# relay_din_board.net
KiCad netlist of a schematic drawn in EAGLE
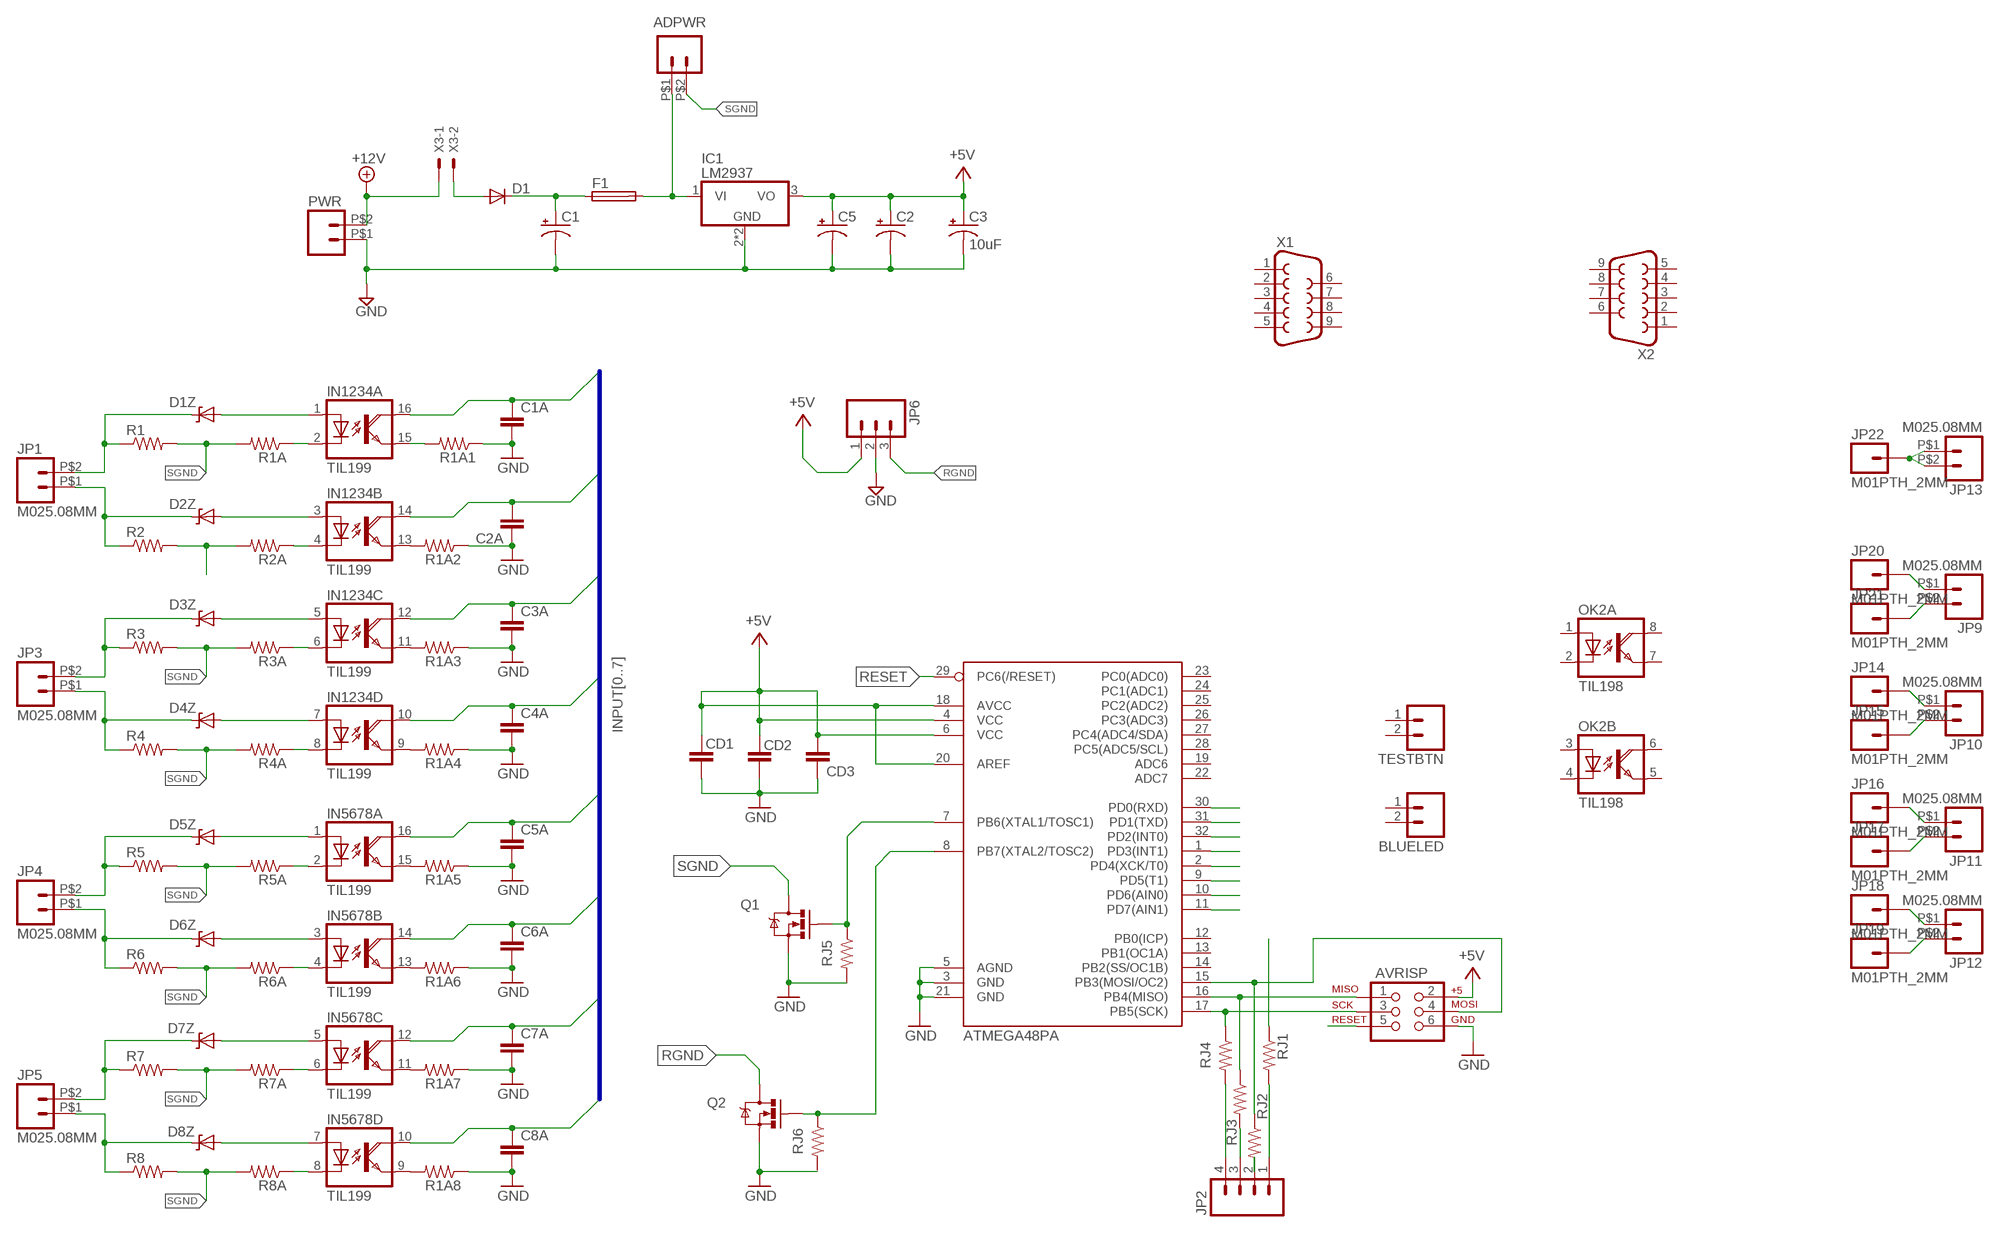
[diagram p0: schematic, sheet 1]

(export (version "E")
  (design (tool "Eeschema 10.0.6"))
  (components
    (comp (ref "ADPWR")
      (value "M025.08MM")
      (footprint "eagle-import:SCREWTERMINAL-5.08MM-2")
      (libsource (lib "eagle-import") (part "M025.08MM"))
    )
    (comp (ref "ATMEGA48PA")
      (value "ATMEGA168")
      (footprint "eagle-import:TQFP32-08")
      (libsource (lib "eagle-import") (part "ATMEGA168"))
    )
    (comp (ref "AVRISP")
      (value "AVR_SPI_PRG_6PTH")
      (footprint "eagle-import:2X3")
      (libsource (lib "eagle-import") (part "AVR_SPI_PRG_6PTH"))
    )
    (comp (ref "BLUELED")
      (value "M02PTH")
      (footprint "eagle-import:1X02")
      (libsource (lib "eagle-import") (part "M02PTH"))
    )
    (comp (ref "C1")
      (value "CPOL-USE5-10.5")
      (footprint "eagle-import:E5-10,5")
      (libsource (lib "eagle-import") (part "CPOL-USE5-10.5"))
    )
    (comp (ref "C1A")
      (value "CAP0805")
      (footprint "eagle-import:0805")
      (libsource (lib "eagle-import") (part "CAP0805"))
    )
    (comp (ref "C2")
      (value "CPOL-US153CLV-0605")
      (footprint "eagle-import:153CLV-0605")
      (libsource (lib "eagle-import") (part "CPOL-US153CLV-0605"))
    )
    (comp (ref "C2A")
      (value "CAP0805")
      (footprint "eagle-import:0805")
      (libsource (lib "eagle-import") (part "CAP0805"))
    )
    (comp (ref "C3")
      (value "10uF")
      (footprint "eagle-import:EIA3216")
      (libsource (lib "eagle-import") (part "10UF-TANT"))
    )
    (comp (ref "C3A")
      (value "CAP0805")
      (footprint "eagle-import:0805")
      (libsource (lib "eagle-import") (part "CAP0805"))
    )
    (comp (ref "C4A")
      (value "CAP0805")
      (footprint "eagle-import:0805")
      (libsource (lib "eagle-import") (part "CAP0805"))
    )
    (comp (ref "C5")
      (value "CPOL-US153CLV-0605")
      (footprint "eagle-import:153CLV-0605")
      (libsource (lib "eagle-import") (part "CPOL-US153CLV-0605"))
    )
    (comp (ref "C5A")
      (value "CAP0805")
      (footprint "eagle-import:0805")
      (libsource (lib "eagle-import") (part "CAP0805"))
    )
    (comp (ref "C6A")
      (value "CAP0805")
      (footprint "eagle-import:0805")
      (libsource (lib "eagle-import") (part "CAP0805"))
    )
    (comp (ref "C7A")
      (value "CAP0805")
      (footprint "eagle-import:0805")
      (libsource (lib "eagle-import") (part "CAP0805"))
    )
    (comp (ref "C8A")
      (value "CAP0805")
      (footprint "eagle-import:0805")
      (libsource (lib "eagle-import") (part "CAP0805"))
    )
    (comp (ref "CD1")
      (value "CAP0805")
      (footprint "eagle-import:0805")
      (libsource (lib "eagle-import") (part "CAP0805"))
    )
    (comp (ref "CD2")
      (value "CAP0805")
      (footprint "eagle-import:0805")
      (libsource (lib "eagle-import") (part "CAP0805"))
    )
    (comp (ref "CD3")
      (value "CAP0805")
      (footprint "eagle-import:0805")
      (libsource (lib "eagle-import") (part "CAP0805"))
    )
    (comp (ref "D1")
      (value "DIODE-C1702-05")
      (footprint "eagle-import:C1702-05")
      (libsource (lib "eagle-import") (part "DIODE-C1702-05"))
    )
    (comp (ref "D1Z")
      (value "DIODE-ZENER-BZT52")
      (footprint "eagle-import:SOD-323")
      (libsource (lib "eagle-import") (part "DIODE-ZENER-BZT52"))
    )
    (comp (ref "D2Z")
      (value "DIODE-ZENER-BZT52")
      (footprint "eagle-import:SOD-323")
      (libsource (lib "eagle-import") (part "DIODE-ZENER-BZT52"))
    )
    (comp (ref "D3Z")
      (value "DIODE-ZENER-BZT52")
      (footprint "eagle-import:SOD-323")
      (libsource (lib "eagle-import") (part "DIODE-ZENER-BZT52"))
    )
    (comp (ref "D4Z")
      (value "DIODE-ZENER-BZT52")
      (footprint "eagle-import:SOD-323")
      (libsource (lib "eagle-import") (part "DIODE-ZENER-BZT52"))
    )
    (comp (ref "D5Z")
      (value "DIODE-ZENER-BZT52")
      (footprint "eagle-import:SOD-323")
      (libsource (lib "eagle-import") (part "DIODE-ZENER-BZT52"))
    )
    (comp (ref "D6Z")
      (value "DIODE-ZENER-BZT52")
      (footprint "eagle-import:SOD-323")
      (libsource (lib "eagle-import") (part "DIODE-ZENER-BZT52"))
    )
    (comp (ref "D7Z")
      (value "DIODE-ZENER-BZT52")
      (footprint "eagle-import:SOD-323")
      (libsource (lib "eagle-import") (part "DIODE-ZENER-BZT52"))
    )
    (comp (ref "D8Z")
      (value "DIODE-ZENER-BZT52")
      (footprint "eagle-import:SOD-323")
      (libsource (lib "eagle-import") (part "DIODE-ZENER-BZT52"))
    )
    (comp (ref "F1")
      (value "GSH15")
      (footprint "eagle-import:GSH15")
      (fields (field (name "MPN") "64900001039"))
      (libsource (lib "eagle-import") (part "GSH15"))
    )
    (comp (ref "IC1")
      (value "LM2937")
      (footprint "eagle-import:TO263-3")
      (libsource (lib "eagle-import") (part "LM2937"))
    )
    (comp (ref "IN1234")
      (value "TIL199")
      (footprint "eagle-import:DIL16")
      (fields (field (name "MPN") "TIL 199"))
      (libsource (lib "eagle-import") (part "TIL199"))
    )
    (comp (ref "IN5678")
      (value "TIL199")
      (footprint "eagle-import:DIL16")
      (fields (field (name "MPN") "TIL 199"))
      (libsource (lib "eagle-import") (part "TIL199"))
    )
    (comp (ref "JP1")
      (value "M025.08MM")
      (footprint "eagle-import:SCREWTERMINAL-5.08MM-2")
      (libsource (lib "eagle-import") (part "M025.08MM"))
    )
    (comp (ref "JP2")
      (value "M04PTH")
      (footprint "eagle-import:1X04")
      (libsource (lib "eagle-import") (part "M04PTH"))
    )
    (comp (ref "JP3")
      (value "M025.08MM")
      (footprint "eagle-import:SCREWTERMINAL-5.08MM-2")
      (libsource (lib "eagle-import") (part "M025.08MM"))
    )
    (comp (ref "JP4")
      (value "M025.08MM")
      (footprint "eagle-import:SCREWTERMINAL-5.08MM-2")
      (libsource (lib "eagle-import") (part "M025.08MM"))
    )
    (comp (ref "JP5")
      (value "M025.08MM")
      (footprint "eagle-import:SCREWTERMINAL-5.08MM-2")
      (libsource (lib "eagle-import") (part "M025.08MM"))
    )
    (comp (ref "JP6")
      (value "M03PTH")
      (footprint "eagle-import:1X03")
      (libsource (lib "eagle-import") (part "M03PTH"))
    )
    (comp (ref "JP9")
      (value "M025.08MM")
      (footprint "eagle-import:SCREWTERMINAL-5.08MM-2")
      (libsource (lib "eagle-import") (part "M025.08MM"))
    )
    (comp (ref "JP10")
      (value "M025.08MM")
      (footprint "eagle-import:SCREWTERMINAL-5.08MM-2")
      (libsource (lib "eagle-import") (part "M025.08MM"))
    )
    (comp (ref "JP11")
      (value "M025.08MM")
      (footprint "eagle-import:SCREWTERMINAL-5.08MM-2")
      (libsource (lib "eagle-import") (part "M025.08MM"))
    )
    (comp (ref "JP12")
      (value "M025.08MM")
      (footprint "eagle-import:SCREWTERMINAL-5.08MM-2")
      (libsource (lib "eagle-import") (part "M025.08MM"))
    )
    (comp (ref "JP13")
      (value "M025.08MM")
      (footprint "eagle-import:SCREWTERMINAL-5.08MM-2")
      (libsource (lib "eagle-import") (part "M025.08MM"))
    )
    (comp (ref "JP14")
      (value "M01PTH_2MM")
      (footprint "eagle-import:1X01_2MM")
      (libsource (lib "eagle-import") (part "M01PTH_2MM"))
    )
    (comp (ref "JP15")
      (value "M01PTH_2MM")
      (footprint "eagle-import:1X01_2MM")
      (libsource (lib "eagle-import") (part "M01PTH_2MM"))
    )
    (comp (ref "JP16")
      (value "M01PTH_2MM")
      (footprint "eagle-import:1X01_2MM")
      (libsource (lib "eagle-import") (part "M01PTH_2MM"))
    )
    (comp (ref "JP17")
      (value "M01PTH_2MM")
      (footprint "eagle-import:1X01_2MM")
      (libsource (lib "eagle-import") (part "M01PTH_2MM"))
    )
    (comp (ref "JP18")
      (value "M01PTH_2MM")
      (footprint "eagle-import:1X01_2MM")
      (libsource (lib "eagle-import") (part "M01PTH_2MM"))
    )
    (comp (ref "JP19")
      (value "M01PTH_2MM")
      (footprint "eagle-import:1X01_2MM")
      (libsource (lib "eagle-import") (part "M01PTH_2MM"))
    )
    (comp (ref "JP20")
      (value "M01PTH_2MM")
      (footprint "eagle-import:1X01_2MM")
      (libsource (lib "eagle-import") (part "M01PTH_2MM"))
    )
    (comp (ref "JP21")
      (value "M01PTH_2MM")
      (footprint "eagle-import:1X01_2MM")
      (libsource (lib "eagle-import") (part "M01PTH_2MM"))
    )
    (comp (ref "JP22")
      (value "M01PTH_2MM")
      (footprint "eagle-import:1X01_2MM")
      (libsource (lib "eagle-import") (part "M01PTH_2MM"))
    )
    (comp (ref "OK2")
      (value "TIL198")
      (footprint "eagle-import:DIL08")
      (libsource (lib "eagle-import") (part "TIL198"))
    )
    (comp (ref "PWR")
      (value "M025.08MM")
      (footprint "eagle-import:SCREWTERMINAL-5.08MM-2")
      (libsource (lib "eagle-import") (part "M025.08MM"))
    )
    (comp (ref "Q1")
      (value "MOSFET-NCHANNELBSS123LT1G")
      (footprint "eagle-import:SOT23")
      (libsource (lib "eagle-import") (part "MOSFET-NCHANNELBSS123LT1G"))
    )
    (comp (ref "Q2")
      (value "MOSFET-NCHANNELBSS123LT1G")
      (footprint "eagle-import:SOT23")
      (libsource (lib "eagle-import") (part "MOSFET-NCHANNELBSS123LT1G"))
    )
    (comp (ref "R1")
      (value "RESISTOR2512")
      (footprint "eagle-import:R2512")
      (libsource (lib "eagle-import") (part "RESISTOR2512"))
    )
    (comp (ref "R1A")
      (value "RESISTOR0805-RES")
      (footprint "eagle-import:0805")
      (libsource (lib "eagle-import") (part "SparkFun-Resistors_RESISTOR0805-RES"))
    )
    (comp (ref "R1A1")
      (value "RESISTOR0805-RES")
      (footprint "eagle-import:0805")
      (libsource (lib "eagle-import") (part "SparkFun-Resistors_RESISTOR0805-RES"))
    )
    (comp (ref "R1A2")
      (value "RESISTOR0805-RES")
      (footprint "eagle-import:0805")
      (libsource (lib "eagle-import") (part "SparkFun-Resistors_RESISTOR0805-RES"))
    )
    (comp (ref "R1A3")
      (value "RESISTOR0805-RES")
      (footprint "eagle-import:0805")
      (libsource (lib "eagle-import") (part "SparkFun-Resistors_RESISTOR0805-RES"))
    )
    (comp (ref "R1A4")
      (value "RESISTOR0805-RES")
      (footprint "eagle-import:0805")
      (libsource (lib "eagle-import") (part "SparkFun-Resistors_RESISTOR0805-RES"))
    )
    (comp (ref "R1A5")
      (value "RESISTOR0805-RES")
      (footprint "eagle-import:0805")
      (libsource (lib "eagle-import") (part "SparkFun-Resistors_RESISTOR0805-RES"))
    )
    (comp (ref "R1A6")
      (value "RESISTOR0805-RES")
      (footprint "eagle-import:0805")
      (libsource (lib "eagle-import") (part "SparkFun-Resistors_RESISTOR0805-RES"))
    )
    (comp (ref "R1A7")
      (value "RESISTOR0805-RES")
      (footprint "eagle-import:0805")
      (libsource (lib "eagle-import") (part "SparkFun-Resistors_RESISTOR0805-RES"))
    )
    (comp (ref "R1A8")
      (value "RESISTOR0805-RES")
      (footprint "eagle-import:0805")
      (libsource (lib "eagle-import") (part "SparkFun-Resistors_RESISTOR0805-RES"))
    )
    (comp (ref "R2")
      (value "RESISTOR2512")
      (footprint "eagle-import:R2512")
      (libsource (lib "eagle-import") (part "RESISTOR2512"))
    )
    (comp (ref "R2A")
      (value "RESISTOR0805-RES")
      (footprint "eagle-import:0805")
      (libsource (lib "eagle-import") (part "SparkFun-Resistors_RESISTOR0805-RES"))
    )
    (comp (ref "R3")
      (value "RESISTOR2512")
      (footprint "eagle-import:R2512")
      (libsource (lib "eagle-import") (part "RESISTOR2512"))
    )
    (comp (ref "R3A")
      (value "RESISTOR0805-RES")
      (footprint "eagle-import:0805")
      (libsource (lib "eagle-import") (part "SparkFun-Resistors_RESISTOR0805-RES"))
    )
    (comp (ref "R4")
      (value "RESISTOR2512")
      (footprint "eagle-import:R2512")
      (libsource (lib "eagle-import") (part "RESISTOR2512"))
    )
    (comp (ref "R4A")
      (value "RESISTOR0805-RES")
      (footprint "eagle-import:0805")
      (libsource (lib "eagle-import") (part "SparkFun-Resistors_RESISTOR0805-RES"))
    )
    (comp (ref "R5")
      (value "RESISTOR2512")
      (footprint "eagle-import:R2512")
      (libsource (lib "eagle-import") (part "RESISTOR2512"))
    )
    (comp (ref "R5A")
      (value "RESISTOR0805-RES")
      (footprint "eagle-import:0805")
      (libsource (lib "eagle-import") (part "SparkFun-Resistors_RESISTOR0805-RES"))
    )
    (comp (ref "R6")
      (value "RESISTOR2512")
      (footprint "eagle-import:R2512")
      (libsource (lib "eagle-import") (part "RESISTOR2512"))
    )
    (comp (ref "R6A")
      (value "RESISTOR0805-RES")
      (footprint "eagle-import:0805")
      (libsource (lib "eagle-import") (part "SparkFun-Resistors_RESISTOR0805-RES"))
    )
    (comp (ref "R7")
      (value "RESISTOR2512")
      (footprint "eagle-import:R2512")
      (libsource (lib "eagle-import") (part "RESISTOR2512"))
    )
    (comp (ref "R7A")
      (value "RESISTOR0805-RES")
      (footprint "eagle-import:0805")
      (libsource (lib "eagle-import") (part "SparkFun-Resistors_RESISTOR0805-RES"))
    )
    (comp (ref "R8")
      (value "RESISTOR2512")
      (footprint "eagle-import:R2512")
      (libsource (lib "eagle-import") (part "RESISTOR2512"))
    )
    (comp (ref "R8A")
      (value "RESISTOR0805-RES")
      (footprint "eagle-import:0805")
      (libsource (lib "eagle-import") (part "SparkFun-Resistors_RESISTOR0805-RES"))
    )
    (comp (ref "RJ1")
      (value "RESISTOR0805-RES")
      (footprint "eagle-import:0805")
      (libsource (lib "eagle-import") (part "SparkFun-Resistors_RESISTOR0805-RES"))
    )
    (comp (ref "RJ2")
      (value "RESISTOR0805-RES")
      (footprint "eagle-import:0805")
      (libsource (lib "eagle-import") (part "SparkFun-Resistors_RESISTOR0805-RES"))
    )
    (comp (ref "RJ3")
      (value "RESISTOR0805-RES")
      (footprint "eagle-import:0805")
      (libsource (lib "eagle-import") (part "SparkFun-Resistors_RESISTOR0805-RES"))
    )
    (comp (ref "RJ4")
      (value "RESISTOR0805-RES")
      (footprint "eagle-import:0805")
      (libsource (lib "eagle-import") (part "SparkFun-Resistors_RESISTOR0805-RES"))
    )
    (comp (ref "RJ5")
      (value "RESISTOR0805-RES")
      (footprint "eagle-import:0805")
      (libsource (lib "eagle-import") (part "SparkFun-Resistors_RESISTOR0805-RES"))
    )
    (comp (ref "RJ6")
      (value "RESISTOR0805-RES")
      (footprint "eagle-import:0805")
      (libsource (lib "eagle-import") (part "SparkFun-Resistors_RESISTOR0805-RES"))
    )
    (comp (ref "TESTBTN")
      (value "M02PTH")
      (footprint "eagle-import:1X02")
      (libsource (lib "eagle-import") (part "M02PTH"))
    )
    (comp (ref "X1")
      (value "DB9FEMALE")
      (footprint "eagle-import:DB9")
      (libsource (lib "eagle-import") (part "DB9FEMALE"))
    )
    (comp (ref "X2")
      (value "DB9MALE")
      (footprint "eagle-import:DB9_MALE")
      (libsource (lib "eagle-import") (part "DB9MALE"))
    )
    (comp (ref "X3")
      (value "22-23-2021")
      (footprint "eagle-import:22-23-2021")
      (fields (field (name "MF") "MOLEX"))
      (libsource (lib "eagle-import") (part "22-23-2021"))
    )
  )
  (nets
    (net (code "1") (name "+5V") (class "Default")
      (node (ref "ATMEGA48PA") (pin "18") (pinfunction "AVCC_18") (pintype "bidirectional"))
      (node (ref "ATMEGA48PA") (pin "20") (pinfunction "AREF_20") (pintype "bidirectional"))
      (node (ref "ATMEGA48PA") (pin "4") (pinfunction "VCC_4") (pintype "bidirectional"))
      (node (ref "ATMEGA48PA") (pin "6") (pinfunction "VCC_6") (pintype "bidirectional"))
      (node (ref "AVRISP") (pin "2") (pinfunction "2_2") (pintype "passive"))
      (node (ref "C2") (pin "+") (pinfunction "+_+") (pintype "passive"))
      (node (ref "C3") (pin "A") (pinfunction "+_A") (pintype "passive"))
      (node (ref "C5") (pin "+") (pinfunction "+_+") (pintype "passive"))
      (node (ref "CD1") (pin "1") (pinfunction "1_1") (pintype "passive"))
      (node (ref "CD2") (pin "1") (pinfunction "1_1") (pintype "passive"))
      (node (ref "CD3") (pin "1") (pinfunction "1_1") (pintype "passive"))
      (node (ref "IC1") (pin "3") (pinfunction "VO_3") (pintype "passive"))
      (node (ref "JP6") (pin "1") (pinfunction "1_1") (pintype "passive"))
    )
    (net (code "2") (name "+12V") (class "Default")
      (node (ref "PWR") (pin "P$2") (pinfunction "2_P$2") (pintype "passive"))
      (node (ref "X3") (pin "1") (pinfunction "S_1") (pintype "passive"))
    )
    (net (code "3") (name "/INPUT0") (class "Default")
      (node (ref "ATMEGA48PA") (pin "30") (pinfunction "PD0(RXD)_30") (pintype "bidirectional"))
      (node (ref "C1A") (pin "1") (pinfunction "1_1") (pintype "passive"))
      (node (ref "IN1234") (pin "16") (pinfunction "COL_16") (pintype "passive"))
    )
    (net (code "4") (name "/INPUT1") (class "Default")
      (node (ref "ATMEGA48PA") (pin "31") (pinfunction "PD1(TXD)_31") (pintype "bidirectional"))
      (node (ref "C2A") (pin "2") (pinfunction "2_2") (pintype "passive"))
      (node (ref "IN1234") (pin "14") (pinfunction "COL_14") (pintype "passive"))
    )
    (net (code "5") (name "/INPUT2") (class "Default")
      (node (ref "ATMEGA48PA") (pin "32") (pinfunction "PD2(INT0)_32") (pintype "bidirectional"))
      (node (ref "C3A") (pin "1") (pinfunction "1_1") (pintype "passive"))
      (node (ref "IN1234") (pin "12") (pinfunction "COL_12") (pintype "passive"))
    )
    (net (code "6") (name "/INPUT3") (class "Default")
      (node (ref "ATMEGA48PA") (pin "1") (pinfunction "PD3(INT1)_1") (pintype "bidirectional"))
      (node (ref "C4A") (pin "1") (pinfunction "1_1") (pintype "passive"))
      (node (ref "IN1234") (pin "10") (pinfunction "COL_10") (pintype "passive"))
    )
    (net (code "7") (name "/INPUT4") (class "Default")
      (node (ref "ATMEGA48PA") (pin "2") (pinfunction "PD4(XCK/T0)_2") (pintype "bidirectional"))
      (node (ref "C5A") (pin "1") (pinfunction "1_1") (pintype "passive"))
      (node (ref "IN5678") (pin "16") (pinfunction "COL_16") (pintype "passive"))
    )
    (net (code "8") (name "/INPUT5") (class "Default")
      (node (ref "ATMEGA48PA") (pin "9") (pinfunction "PD5(T1)_9") (pintype "bidirectional"))
      (node (ref "C6A") (pin "1") (pinfunction "1_1") (pintype "passive"))
      (node (ref "IN5678") (pin "14") (pinfunction "COL_14") (pintype "passive"))
    )
    (net (code "9") (name "/INPUT6") (class "Default")
      (node (ref "ATMEGA48PA") (pin "10") (pinfunction "PD6(AIN0)_10") (pintype "bidirectional"))
      (node (ref "C7A") (pin "1") (pinfunction "1_1") (pintype "passive"))
      (node (ref "IN5678") (pin "12") (pinfunction "COL_12") (pintype "passive"))
    )
    (net (code "10") (name "/INPUT7") (class "Default")
      (node (ref "ATMEGA48PA") (pin "11") (pinfunction "PD7(AIN1)_11") (pintype "bidirectional"))
      (node (ref "C8A") (pin "1") (pinfunction "1_1") (pintype "passive"))
      (node (ref "IN5678") (pin "10") (pinfunction "COL_10") (pintype "passive"))
    )
    (net (code "12") (name "GND") (class "Default")
      (node (ref "ATMEGA48PA") (pin "21") (pinfunction "GND_21") (pintype "bidirectional"))
      (node (ref "ATMEGA48PA") (pin "3") (pinfunction "GND_3") (pintype "bidirectional"))
      (node (ref "ATMEGA48PA") (pin "5") (pinfunction "AGND_5") (pintype "bidirectional"))
      (node (ref "AVRISP") (pin "6") (pinfunction "6_6") (pintype "passive"))
      (node (ref "C1") (pin "-") (pinfunction "-_-") (pintype "passive"))
      (node (ref "C1A") (pin "2") (pinfunction "2_2") (pintype "passive"))
      (node (ref "C2") (pin "-") (pinfunction "-_-") (pintype "passive"))
      (node (ref "C2A") (pin "1") (pinfunction "1_1") (pintype "passive"))
      (node (ref "C3") (pin "C") (pinfunction "-_C") (pintype "passive"))
      (node (ref "C3A") (pin "2") (pinfunction "2_2") (pintype "passive"))
      (node (ref "C4A") (pin "2") (pinfunction "2_2") (pintype "passive"))
      (node (ref "C5") (pin "-") (pinfunction "-_-") (pintype "passive"))
      (node (ref "C5A") (pin "2") (pinfunction "2_2") (pintype "passive"))
      (node (ref "C6A") (pin "2") (pinfunction "2_2") (pintype "passive"))
      (node (ref "C7A") (pin "2") (pinfunction "2_2") (pintype "passive"))
      (node (ref "C8A") (pin "2") (pinfunction "2_2") (pintype "passive"))
      (node (ref "CD1") (pin "2") (pinfunction "2_2") (pintype "passive"))
      (node (ref "CD2") (pin "2") (pinfunction "2_2") (pintype "passive"))
      (node (ref "CD3") (pin "2") (pinfunction "2_2") (pintype "passive"))
      (node (ref "IC1") (pin "2") (pinfunction "GND_2") (pintype "passive"))
      (node (ref "IC1") (pin "TAB") (pinfunction "GND_TAB") (pintype "passive"))
      (node (ref "JP6") (pin "2") (pinfunction "2_2") (pintype "passive"))
      (node (ref "PWR") (pin "P$1") (pinfunction "1_P$1") (pintype "passive"))
      (node (ref "Q1") (pin "2") (pinfunction "S_2") (pintype "passive"))
      (node (ref "Q2") (pin "2") (pinfunction "S_2") (pintype "passive"))
      (node (ref "R1A1") (pin "1") (pinfunction "1_1") (pintype "passive"))
      (node (ref "R1A2") (pin "1") (pinfunction "1_1") (pintype "passive"))
      (node (ref "R1A3") (pin "1") (pinfunction "1_1") (pintype "passive"))
      (node (ref "R1A4") (pin "1") (pinfunction "1_1") (pintype "passive"))
      (node (ref "R1A5") (pin "1") (pinfunction "1_1") (pintype "passive"))
      (node (ref "R1A6") (pin "1") (pinfunction "1_1") (pintype "passive"))
      (node (ref "R1A7") (pin "1") (pinfunction "1_1") (pintype "passive"))
      (node (ref "R1A8") (pin "1") (pinfunction "1_1") (pintype "passive"))
      (node (ref "RJ5") (pin "2") (pinfunction "2_2") (pintype "passive"))
    )
    (net (code "13") (name "Net-(ADPWR-1)") (class "Default")
      (node (ref "ADPWR") (pin "P$1") (pinfunction "1_P$1") (pintype "passive"))
      (node (ref "F1") (pin "2") (pinfunction "2_2") (pintype "passive"))
      (node (ref "IC1") (pin "1") (pinfunction "VI_1") (pintype "input"))
    )
    (net (code "14") (name "Net-(ATMEGA48PA-PB3(MOSI{slash}OC2))") (class "Default")
      (node (ref "ATMEGA48PA") (pin "15") (pinfunction "PB3(MOSI/OC2)_15") (pintype "bidirectional"))
      (node (ref "AVRISP") (pin "4") (pinfunction "4_4") (pintype "passive"))
      (node (ref "RJ2") (pin "1") (pinfunction "1_1") (pintype "passive"))
    )
    (net (code "15") (name "Net-(ATMEGA48PA-PB4(MISO))") (class "Default")
      (node (ref "ATMEGA48PA") (pin "16") (pinfunction "PB4(MISO)_16") (pintype "bidirectional"))
      (node (ref "AVRISP") (pin "1") (pinfunction "1_1") (pintype "passive"))
      (node (ref "RJ3") (pin "1") (pinfunction "1_1") (pintype "passive"))
    )
    (net (code "16") (name "Net-(ATMEGA48PA-PB5(SCK))") (class "Default")
      (node (ref "ATMEGA48PA") (pin "17") (pinfunction "PB5(SCK)_17") (pintype "bidirectional"))
      (node (ref "AVRISP") (pin "3") (pinfunction "3_3") (pintype "passive"))
      (node (ref "RJ4") (pin "1") (pinfunction "1_1") (pintype "passive"))
    )
    (net (code "17") (name "Net-(ATMEGA48PA-PB6(XTAL1{slash}TOSC1))") (class "Default")
      (node (ref "ATMEGA48PA") (pin "7") (pinfunction "PB6(XTAL1/TOSC1)_7") (pintype "bidirectional"))
      (node (ref "Q1") (pin "1") (pinfunction "G_1") (pintype "passive"))
      (node (ref "RJ5") (pin "1") (pinfunction "1_1") (pintype "passive"))
    )
    (net (code "18") (name "Net-(ATMEGA48PA-PB7(XTAL2{slash}TOSC2))") (class "Default")
      (node (ref "ATMEGA48PA") (pin "8") (pinfunction "PB7(XTAL2/TOSC2)_8") (pintype "bidirectional"))
      (node (ref "Q2") (pin "1") (pinfunction "G_1") (pintype "passive"))
      (node (ref "RJ6") (pin "1") (pinfunction "1_1") (pintype "passive"))
    )
    (net (code "19") (name "Net-(C1-Pad+)") (class "Default")
      (node (ref "C1") (pin "+") (pinfunction "+_+") (pintype "passive"))
      (node (ref "D1") (pin "C") (pinfunction "C_C") (pintype "passive"))
      (node (ref "F1") (pin "1") (pinfunction "1_1") (pintype "passive"))
    )
    (net (code "20") (name "Net-(D1Z-A)") (class "Default")
      (node (ref "D1Z") (pin "2") (pinfunction "A_2") (pintype "passive"))
      (node (ref "IN1234") (pin "1") (pinfunction "A_1") (pintype "passive"))
    )
    (net (code "21") (name "Net-(D1Z-C)") (class "Default")
      (node (ref "D1Z") (pin "1") (pinfunction "C_1") (pintype "passive"))
      (node (ref "JP1") (pin "P$2") (pinfunction "2_P$2") (pintype "passive"))
      (node (ref "R1") (pin "1") (pinfunction "1_1") (pintype "passive"))
    )
    (net (code "22") (name "Net-(D2Z-A)") (class "Default")
      (node (ref "D2Z") (pin "2") (pinfunction "A_2") (pintype "passive"))
      (node (ref "IN1234") (pin "3") (pinfunction "A_3") (pintype "passive"))
    )
    (net (code "23") (name "Net-(D2Z-C)") (class "Default")
      (node (ref "D2Z") (pin "1") (pinfunction "C_1") (pintype "passive"))
      (node (ref "JP1") (pin "P$1") (pinfunction "1_P$1") (pintype "passive"))
      (node (ref "R2") (pin "1") (pinfunction "1_1") (pintype "passive"))
    )
    (net (code "24") (name "Net-(D3Z-A)") (class "Default")
      (node (ref "D3Z") (pin "2") (pinfunction "A_2") (pintype "passive"))
      (node (ref "IN1234") (pin "5") (pinfunction "A_5") (pintype "passive"))
    )
    (net (code "25") (name "Net-(D3Z-C)") (class "Default")
      (node (ref "D3Z") (pin "1") (pinfunction "C_1") (pintype "passive"))
      (node (ref "JP3") (pin "P$2") (pinfunction "2_P$2") (pintype "passive"))
      (node (ref "R3") (pin "1") (pinfunction "1_1") (pintype "passive"))
    )
    (net (code "26") (name "Net-(D4Z-A)") (class "Default")
      (node (ref "D4Z") (pin "2") (pinfunction "A_2") (pintype "passive"))
      (node (ref "IN1234") (pin "7") (pinfunction "A_7") (pintype "passive"))
    )
    (net (code "27") (name "Net-(D4Z-C)") (class "Default")
      (node (ref "D4Z") (pin "1") (pinfunction "C_1") (pintype "passive"))
      (node (ref "JP3") (pin "P$1") (pinfunction "1_P$1") (pintype "passive"))
      (node (ref "R4") (pin "1") (pinfunction "1_1") (pintype "passive"))
    )
    (net (code "28") (name "Net-(D5Z-A)") (class "Default")
      (node (ref "D5Z") (pin "2") (pinfunction "A_2") (pintype "passive"))
      (node (ref "IN5678") (pin "1") (pinfunction "A_1") (pintype "passive"))
    )
    (net (code "29") (name "Net-(D5Z-C)") (class "Default")
      (node (ref "D5Z") (pin "1") (pinfunction "C_1") (pintype "passive"))
      (node (ref "JP4") (pin "P$2") (pinfunction "2_P$2") (pintype "passive"))
      (node (ref "R5") (pin "1") (pinfunction "1_1") (pintype "passive"))
    )
    (net (code "30") (name "Net-(D6Z-A)") (class "Default")
      (node (ref "D6Z") (pin "2") (pinfunction "A_2") (pintype "passive"))
      (node (ref "IN5678") (pin "3") (pinfunction "A_3") (pintype "passive"))
    )
    (net (code "31") (name "Net-(D6Z-C)") (class "Default")
      (node (ref "D6Z") (pin "1") (pinfunction "C_1") (pintype "passive"))
      (node (ref "JP4") (pin "P$1") (pinfunction "1_P$1") (pintype "passive"))
      (node (ref "R6") (pin "1") (pinfunction "1_1") (pintype "passive"))
    )
    (net (code "32") (name "Net-(D7Z-A)") (class "Default")
      (node (ref "D7Z") (pin "2") (pinfunction "A_2") (pintype "passive"))
      (node (ref "IN5678") (pin "5") (pinfunction "A_5") (pintype "passive"))
    )
    (net (code "33") (name "Net-(D7Z-C)") (class "Default")
      (node (ref "D7Z") (pin "1") (pinfunction "C_1") (pintype "passive"))
      (node (ref "JP5") (pin "P$2") (pinfunction "2_P$2") (pintype "passive"))
      (node (ref "R7") (pin "1") (pinfunction "1_1") (pintype "passive"))
    )
    (net (code "34") (name "Net-(D8Z-A)") (class "Default")
      (node (ref "D8Z") (pin "2") (pinfunction "A_2") (pintype "passive"))
      (node (ref "IN5678") (pin "7") (pinfunction "A_7") (pintype "passive"))
    )
    (net (code "35") (name "Net-(D8Z-C)") (class "Default")
      (node (ref "D8Z") (pin "1") (pinfunction "C_1") (pintype "passive"))
      (node (ref "JP5") (pin "P$1") (pinfunction "1_P$1") (pintype "passive"))
      (node (ref "R8") (pin "1") (pinfunction "1_1") (pintype "passive"))
    )
    (net (code "36") (name "Net-(IN1234A-C)") (class "Default")
      (node (ref "IN1234") (pin "2") (pinfunction "C_2") (pintype "passive"))
      (node (ref "R1A") (pin "1") (pinfunction "1_1") (pintype "passive"))
    )
    (net (code "37") (name "Net-(IN1234A-EMI)") (class "Default")
      (node (ref "IN1234") (pin "15") (pinfunction "EMI_15") (pintype "passive"))
      (node (ref "R1A1") (pin "2") (pinfunction "2_2") (pintype "passive"))
    )
    (net (code "38") (name "Net-(IN1234B-C)") (class "Default")
      (node (ref "IN1234") (pin "4") (pinfunction "C_4") (pintype "passive"))
      (node (ref "R2A") (pin "1") (pinfunction "1_1") (pintype "passive"))
    )
    (net (code "39") (name "Net-(IN1234B-EMI)") (class "Default")
      (node (ref "IN1234") (pin "13") (pinfunction "EMI_13") (pintype "passive"))
      (node (ref "R1A2") (pin "2") (pinfunction "2_2") (pintype "passive"))
    )
    (net (code "40") (name "Net-(IN1234C-C)") (class "Default")
      (node (ref "IN1234") (pin "6") (pinfunction "C_6") (pintype "passive"))
      (node (ref "R3A") (pin "1") (pinfunction "1_1") (pintype "passive"))
    )
    (net (code "41") (name "Net-(IN1234C-EMI)") (class "Default")
      (node (ref "IN1234") (pin "11") (pinfunction "EMI_11") (pintype "passive"))
      (node (ref "R1A3") (pin "2") (pinfunction "2_2") (pintype "passive"))
    )
    (net (code "42") (name "Net-(IN1234D-C)") (class "Default")
      (node (ref "IN1234") (pin "8") (pinfunction "C_8") (pintype "passive"))
      (node (ref "R4A") (pin "1") (pinfunction "1_1") (pintype "passive"))
    )
    (net (code "43") (name "Net-(IN1234D-EMI)") (class "Default")
      (node (ref "IN1234") (pin "9") (pinfunction "EMI_9") (pintype "passive"))
      (node (ref "R1A4") (pin "2") (pinfunction "2_2") (pintype "passive"))
    )
    (net (code "44") (name "Net-(IN5678A-C)") (class "Default")
      (node (ref "IN5678") (pin "2") (pinfunction "C_2") (pintype "passive"))
      (node (ref "R5A") (pin "1") (pinfunction "1_1") (pintype "passive"))
    )
    (net (code "45") (name "Net-(IN5678A-EMI)") (class "Default")
      (node (ref "IN5678") (pin "15") (pinfunction "EMI_15") (pintype "passive"))
      (node (ref "R1A5") (pin "2") (pinfunction "2_2") (pintype "passive"))
    )
    (net (code "46") (name "Net-(IN5678B-C)") (class "Default")
      (node (ref "IN5678") (pin "4") (pinfunction "C_4") (pintype "passive"))
      (node (ref "R6A") (pin "1") (pinfunction "1_1") (pintype "passive"))
    )
    (net (code "47") (name "Net-(IN5678B-EMI)") (class "Default")
      (node (ref "IN5678") (pin "13") (pinfunction "EMI_13") (pintype "passive"))
      (node (ref "R1A6") (pin "2") (pinfunction "2_2") (pintype "passive"))
    )
    (net (code "48") (name "Net-(IN5678C-C)") (class "Default")
      (node (ref "IN5678") (pin "6") (pinfunction "C_6") (pintype "passive"))
      (node (ref "R7A") (pin "1") (pinfunction "1_1") (pintype "passive"))
    )
    (net (code "49") (name "Net-(IN5678C-EMI)") (class "Default")
      (node (ref "IN5678") (pin "11") (pinfunction "EMI_11") (pintype "passive"))
      (node (ref "R1A7") (pin "2") (pinfunction "2_2") (pintype "passive"))
    )
    (net (code "50") (name "Net-(IN5678D-C)") (class "Default")
      (node (ref "IN5678") (pin "8") (pinfunction "C_8") (pintype "passive"))
      (node (ref "R8A") (pin "1") (pinfunction "1_1") (pintype "passive"))
    )
    (net (code "51") (name "Net-(IN5678D-EMI)") (class "Default")
      (node (ref "IN5678") (pin "9") (pinfunction "EMI_9") (pintype "passive"))
      (node (ref "R1A8") (pin "2") (pinfunction "2_2") (pintype "passive"))
    )
    (net (code "52") (name "Net-(JP2-Pad1)") (class "Default")
      (node (ref "JP2") (pin "1") (pinfunction "1_1") (pintype "passive"))
      (node (ref "RJ1") (pin "2") (pinfunction "2_2") (pintype "passive"))
    )
    (net (code "53") (name "Net-(JP2-Pad2)") (class "Default")
      (node (ref "JP2") (pin "2") (pinfunction "2_2") (pintype "passive"))
      (node (ref "RJ2") (pin "2") (pinfunction "2_2") (pintype "passive"))
    )
    (net (code "54") (name "Net-(JP2-Pad3)") (class "Default")
      (node (ref "JP2") (pin "3") (pinfunction "3_3") (pintype "passive"))
      (node (ref "RJ3") (pin "2") (pinfunction "2_2") (pintype "passive"))
    )
    (net (code "55") (name "Net-(JP2-Pad4)") (class "Default")
      (node (ref "JP2") (pin "4") (pinfunction "4_4") (pintype "passive"))
      (node (ref "RJ4") (pin "2") (pinfunction "2_2") (pintype "passive"))
    )
    (net (code "56") (name "Net-(JP9-1)") (class "Default")
      (node (ref "JP20") (pin "1") (pinfunction "1_1") (pintype "passive"))
      (node (ref "JP9") (pin "P$1") (pinfunction "1_P$1") (pintype "passive"))
    )
    (net (code "57") (name "Net-(JP9-2)") (class "Default")
      (node (ref "JP21") (pin "1") (pinfunction "1_1") (pintype "passive"))
      (node (ref "JP9") (pin "P$2") (pinfunction "2_P$2") (pintype "passive"))
    )
    (net (code "58") (name "Net-(JP10-1)") (class "Default")
      (node (ref "JP10") (pin "P$1") (pinfunction "1_P$1") (pintype "passive"))
      (node (ref "JP14") (pin "1") (pinfunction "1_1") (pintype "passive"))
    )
    (net (code "59") (name "Net-(JP10-2)") (class "Default")
      (node (ref "JP10") (pin "P$2") (pinfunction "2_P$2") (pintype "passive"))
      (node (ref "JP15") (pin "1") (pinfunction "1_1") (pintype "passive"))
    )
    (net (code "60") (name "Net-(JP11-1)") (class "Default")
      (node (ref "JP11") (pin "P$1") (pinfunction "1_P$1") (pintype "passive"))
      (node (ref "JP16") (pin "1") (pinfunction "1_1") (pintype "passive"))
    )
    (net (code "61") (name "Net-(JP11-2)") (class "Default")
      (node (ref "JP11") (pin "P$2") (pinfunction "2_P$2") (pintype "passive"))
      (node (ref "JP17") (pin "1") (pinfunction "1_1") (pintype "passive"))
    )
    (net (code "62") (name "Net-(JP12-1)") (class "Default")
      (node (ref "JP12") (pin "P$1") (pinfunction "1_P$1") (pintype "passive"))
      (node (ref "JP18") (pin "1") (pinfunction "1_1") (pintype "passive"))
    )
    (net (code "63") (name "Net-(JP12-2)") (class "Default")
      (node (ref "JP12") (pin "P$2") (pinfunction "2_P$2") (pintype "passive"))
      (node (ref "JP19") (pin "1") (pinfunction "1_1") (pintype "passive"))
    )
    (net (code "64") (name "Net-(JP13-1)") (class "Default")
      (node (ref "JP13") (pin "P$1") (pinfunction "1_P$1") (pintype "passive"))
      (node (ref "JP13") (pin "P$2") (pinfunction "2_P$2") (pintype "passive"))
      (node (ref "JP22") (pin "1") (pinfunction "1_1") (pintype "passive"))
    )
    (net (code "65") (name "Net-(X3B-S)") (class "Default")
      (node (ref "D1") (pin "A") (pinfunction "A_A") (pintype "passive"))
      (node (ref "X3") (pin "2") (pinfunction "S_2") (pintype "passive"))
    )
    (net (code "66") (name "RESET") (class "Default")
      (node (ref "ATMEGA48PA") (pin "29") (pinfunction "PC6(/RESET)_29") (pintype "bidirectional"))
      (node (ref "AVRISP") (pin "5") (pinfunction "5_5") (pintype "passive"))
    )
    (net (code "67") (name "RGND") (class "Default")
      (node (ref "JP6") (pin "3") (pinfunction "3_3") (pintype "passive"))
      (node (ref "Q2") (pin "3") (pinfunction "D_3") (pintype "passive"))
    )
    (net (code "68") (name "SGND") (class "Default")
      (node (ref "ADPWR") (pin "P$2") (pinfunction "2_P$2") (pintype "passive"))
      (node (ref "Q1") (pin "3") (pinfunction "D_3") (pintype "passive"))
      (node (ref "R1") (pin "2") (pinfunction "2_2") (pintype "passive"))
      (node (ref "R1A") (pin "2") (pinfunction "2_2") (pintype "passive"))
      (node (ref "R2") (pin "2") (pinfunction "2_2") (pintype "passive"))
      (node (ref "R2A") (pin "2") (pinfunction "2_2") (pintype "passive"))
      (node (ref "R3") (pin "2") (pinfunction "2_2") (pintype "passive"))
      (node (ref "R3A") (pin "2") (pinfunction "2_2") (pintype "passive"))
      (node (ref "R4") (pin "2") (pinfunction "2_2") (pintype "passive"))
      (node (ref "R4A") (pin "2") (pinfunction "2_2") (pintype "passive"))
      (node (ref "R5") (pin "2") (pinfunction "2_2") (pintype "passive"))
      (node (ref "R5A") (pin "2") (pinfunction "2_2") (pintype "passive"))
      (node (ref "R6") (pin "2") (pinfunction "2_2") (pintype "passive"))
      (node (ref "R6A") (pin "2") (pinfunction "2_2") (pintype "passive"))
      (node (ref "R7") (pin "2") (pinfunction "2_2") (pintype "passive"))
      (node (ref "R7A") (pin "2") (pinfunction "2_2") (pintype "passive"))
      (node (ref "R8") (pin "2") (pinfunction "2_2") (pintype "passive"))
      (node (ref "R8A") (pin "2") (pinfunction "2_2") (pintype "passive"))
    )
    (net (code "69") (name "unconnected-(ATMEGA48PA-ADC6-Pad19)") (class "Default")
      (node (ref "ATMEGA48PA") (pin "19") (pinfunction "ADC6_19") (pintype "bidirectional"))
    )
    (net (code "70") (name "unconnected-(ATMEGA48PA-ADC7-Pad22)") (class "Default")
      (node (ref "ATMEGA48PA") (pin "22") (pinfunction "ADC7_22") (pintype "bidirectional"))
    )
    (net (code "71") (name "unconnected-(ATMEGA48PA-PB0(ICP)-Pad12)") (class "Default")
      (node (ref "ATMEGA48PA") (pin "12") (pinfunction "PB0(ICP)_12") (pintype "bidirectional"))
    )
    (net (code "72") (name "unconnected-(ATMEGA48PA-PB1(OC1A)-Pad13)") (class "Default")
      (node (ref "ATMEGA48PA") (pin "13") (pinfunction "PB1(OC1A)_13") (pintype "bidirectional"))
    )
    (net (code "73") (name "unconnected-(ATMEGA48PA-PB2(SS{slash}OC1B)-Pad14)") (class "Default")
      (node (ref "ATMEGA48PA") (pin "14") (pinfunction "PB2(SS/OC1B)_14") (pintype "bidirectional"))
    )
    (net (code "74") (name "unconnected-(ATMEGA48PA-PC0(ADC0)-Pad23)") (class "Default")
      (node (ref "ATMEGA48PA") (pin "23") (pinfunction "PC0(ADC0)_23") (pintype "bidirectional"))
    )
    (net (code "75") (name "unconnected-(ATMEGA48PA-PC1(ADC1)-Pad24)") (class "Default")
      (node (ref "ATMEGA48PA") (pin "24") (pinfunction "PC1(ADC1)_24") (pintype "bidirectional"))
    )
    (net (code "76") (name "unconnected-(ATMEGA48PA-PC2(ADC2)-Pad25)") (class "Default")
      (node (ref "ATMEGA48PA") (pin "25") (pinfunction "PC2(ADC2)_25") (pintype "bidirectional"))
    )
    (net (code "77") (name "unconnected-(ATMEGA48PA-PC3(ADC3)-Pad26)") (class "Default")
      (node (ref "ATMEGA48PA") (pin "26") (pinfunction "PC3(ADC3)_26") (pintype "bidirectional"))
    )
    (net (code "78") (name "unconnected-(ATMEGA48PA-PC4(ADC4{slash}SDA)-Pad27)") (class "Default")
      (node (ref "ATMEGA48PA") (pin "27") (pinfunction "PC4(ADC4/SDA)_27") (pintype "bidirectional"))
    )
    (net (code "79") (name "unconnected-(ATMEGA48PA-PC5(ADC5{slash}SCL)-Pad28)") (class "Default")
      (node (ref "ATMEGA48PA") (pin "28") (pinfunction "PC5(ADC5/SCL)_28") (pintype "bidirectional"))
    )
    (net (code "80") (name "unconnected-(BLUELED-Pad1)") (class "Default")
      (node (ref "BLUELED") (pin "1") (pinfunction "1_1") (pintype "passive"))
    )
    (net (code "81") (name "unconnected-(BLUELED-Pad2)") (class "Default")
      (node (ref "BLUELED") (pin "2") (pinfunction "2_2") (pintype "passive"))
    )
    (net (code "82") (name "unconnected-(OK2A-A-Pad1)") (class "Default")
      (node (ref "OK2") (pin "1") (pinfunction "A_1") (pintype "passive"))
    )
    (net (code "83") (name "unconnected-(OK2A-C-Pad2)") (class "Default")
      (node (ref "OK2") (pin "2") (pinfunction "C_2") (pintype "passive"))
    )
    (net (code "84") (name "unconnected-(OK2A-COL-Pad8)") (class "Default")
      (node (ref "OK2") (pin "8") (pinfunction "COL_8") (pintype "passive"))
    )
    (net (code "85") (name "unconnected-(OK2A-EMI-Pad7)") (class "Default")
      (node (ref "OK2") (pin "7") (pinfunction "EMI_7") (pintype "passive"))
    )
    (net (code "86") (name "unconnected-(OK2B-A-Pad3)") (class "Default")
      (node (ref "OK2") (pin "3") (pinfunction "A_3") (pintype "passive"))
    )
    (net (code "87") (name "unconnected-(OK2B-C-Pad4)") (class "Default")
      (node (ref "OK2") (pin "4") (pinfunction "C_4") (pintype "passive"))
    )
    (net (code "88") (name "unconnected-(OK2B-COL-Pad6)") (class "Default")
      (node (ref "OK2") (pin "6") (pinfunction "COL_6") (pintype "passive"))
    )
    (net (code "89") (name "unconnected-(OK2B-EMI-Pad5)") (class "Default")
      (node (ref "OK2") (pin "5") (pinfunction "EMI_5") (pintype "passive"))
    )
    (net (code "90") (name "unconnected-(RJ1-Pad1)") (class "Default")
      (node (ref "RJ1") (pin "1") (pinfunction "1_1") (pintype "passive"))
    )
    (net (code "91") (name "unconnected-(RJ6-Pad2)") (class "Default")
      (node (ref "RJ6") (pin "2") (pinfunction "2_2") (pintype "passive"))
    )
    (net (code "92") (name "unconnected-(TESTBTN-Pad1)") (class "Default")
      (node (ref "TESTBTN") (pin "1") (pinfunction "1_1") (pintype "passive"))
    )
    (net (code "93") (name "unconnected-(TESTBTN-Pad2)") (class "Default")
      (node (ref "TESTBTN") (pin "2") (pinfunction "2_2") (pintype "passive"))
    )
    (net (code "94") (name "unconnected-(X1-Pad1)") (class "Default")
      (node (ref "X1") (pin "1") (pinfunction "1_1") (pintype "passive"))
    )
    (net (code "95") (name "unconnected-(X1-Pad2)") (class "Default")
      (node (ref "X1") (pin "2") (pinfunction "2_2") (pintype "passive"))
    )
    (net (code "96") (name "unconnected-(X1-Pad3)") (class "Default")
      (node (ref "X1") (pin "3") (pinfunction "3_3") (pintype "passive"))
    )
    (net (code "97") (name "unconnected-(X1-Pad4)") (class "Default")
      (node (ref "X1") (pin "4") (pinfunction "4_4") (pintype "passive"))
    )
    (net (code "98") (name "unconnected-(X1-Pad5)") (class "Default")
      (node (ref "X1") (pin "5") (pinfunction "5_5") (pintype "passive"))
    )
    (net (code "99") (name "unconnected-(X1-Pad6)") (class "Default")
      (node (ref "X1") (pin "6") (pinfunction "6_6") (pintype "passive"))
    )
    (net (code "100") (name "unconnected-(X1-Pad7)") (class "Default")
      (node (ref "X1") (pin "7") (pinfunction "7_7") (pintype "passive"))
    )
    (net (code "101") (name "unconnected-(X1-Pad8)") (class "Default")
      (node (ref "X1") (pin "8") (pinfunction "8_8") (pintype "passive"))
    )
    (net (code "102") (name "unconnected-(X1-Pad9)") (class "Default")
      (node (ref "X1") (pin "9") (pinfunction "9_9") (pintype "passive"))
    )
    (net (code "103") (name "unconnected-(X2-Pad1)") (class "Default")
      (node (ref "X2") (pin "1") (pinfunction "1_1") (pintype "passive"))
    )
    (net (code "104") (name "unconnected-(X2-Pad2)") (class "Default")
      (node (ref "X2") (pin "2") (pinfunction "2_2") (pintype "passive"))
    )
    (net (code "105") (name "unconnected-(X2-Pad3)") (class "Default")
      (node (ref "X2") (pin "3") (pinfunction "3_3") (pintype "passive"))
    )
    (net (code "106") (name "unconnected-(X2-Pad4)") (class "Default")
      (node (ref "X2") (pin "4") (pinfunction "4_4") (pintype "passive"))
    )
    (net (code "107") (name "unconnected-(X2-Pad5)") (class "Default")
      (node (ref "X2") (pin "5") (pinfunction "5_5") (pintype "passive"))
    )
    (net (code "108") (name "unconnected-(X2-Pad6)") (class "Default")
      (node (ref "X2") (pin "6") (pinfunction "6_6") (pintype "passive"))
    )
    (net (code "109") (name "unconnected-(X2-Pad7)") (class "Default")
      (node (ref "X2") (pin "7") (pinfunction "7_7") (pintype "passive"))
    )
    (net (code "110") (name "unconnected-(X2-Pad8)") (class "Default")
      (node (ref "X2") (pin "8") (pinfunction "8_8") (pintype "passive"))
    )
    (net (code "111") (name "unconnected-(X2-Pad9)") (class "Default")
      (node (ref "X2") (pin "9") (pinfunction "9_9") (pintype "passive"))
    )
  )
)
